# GPS_radiologger_v14.net
KiCad netlist of a schematic drawn in EAGLE
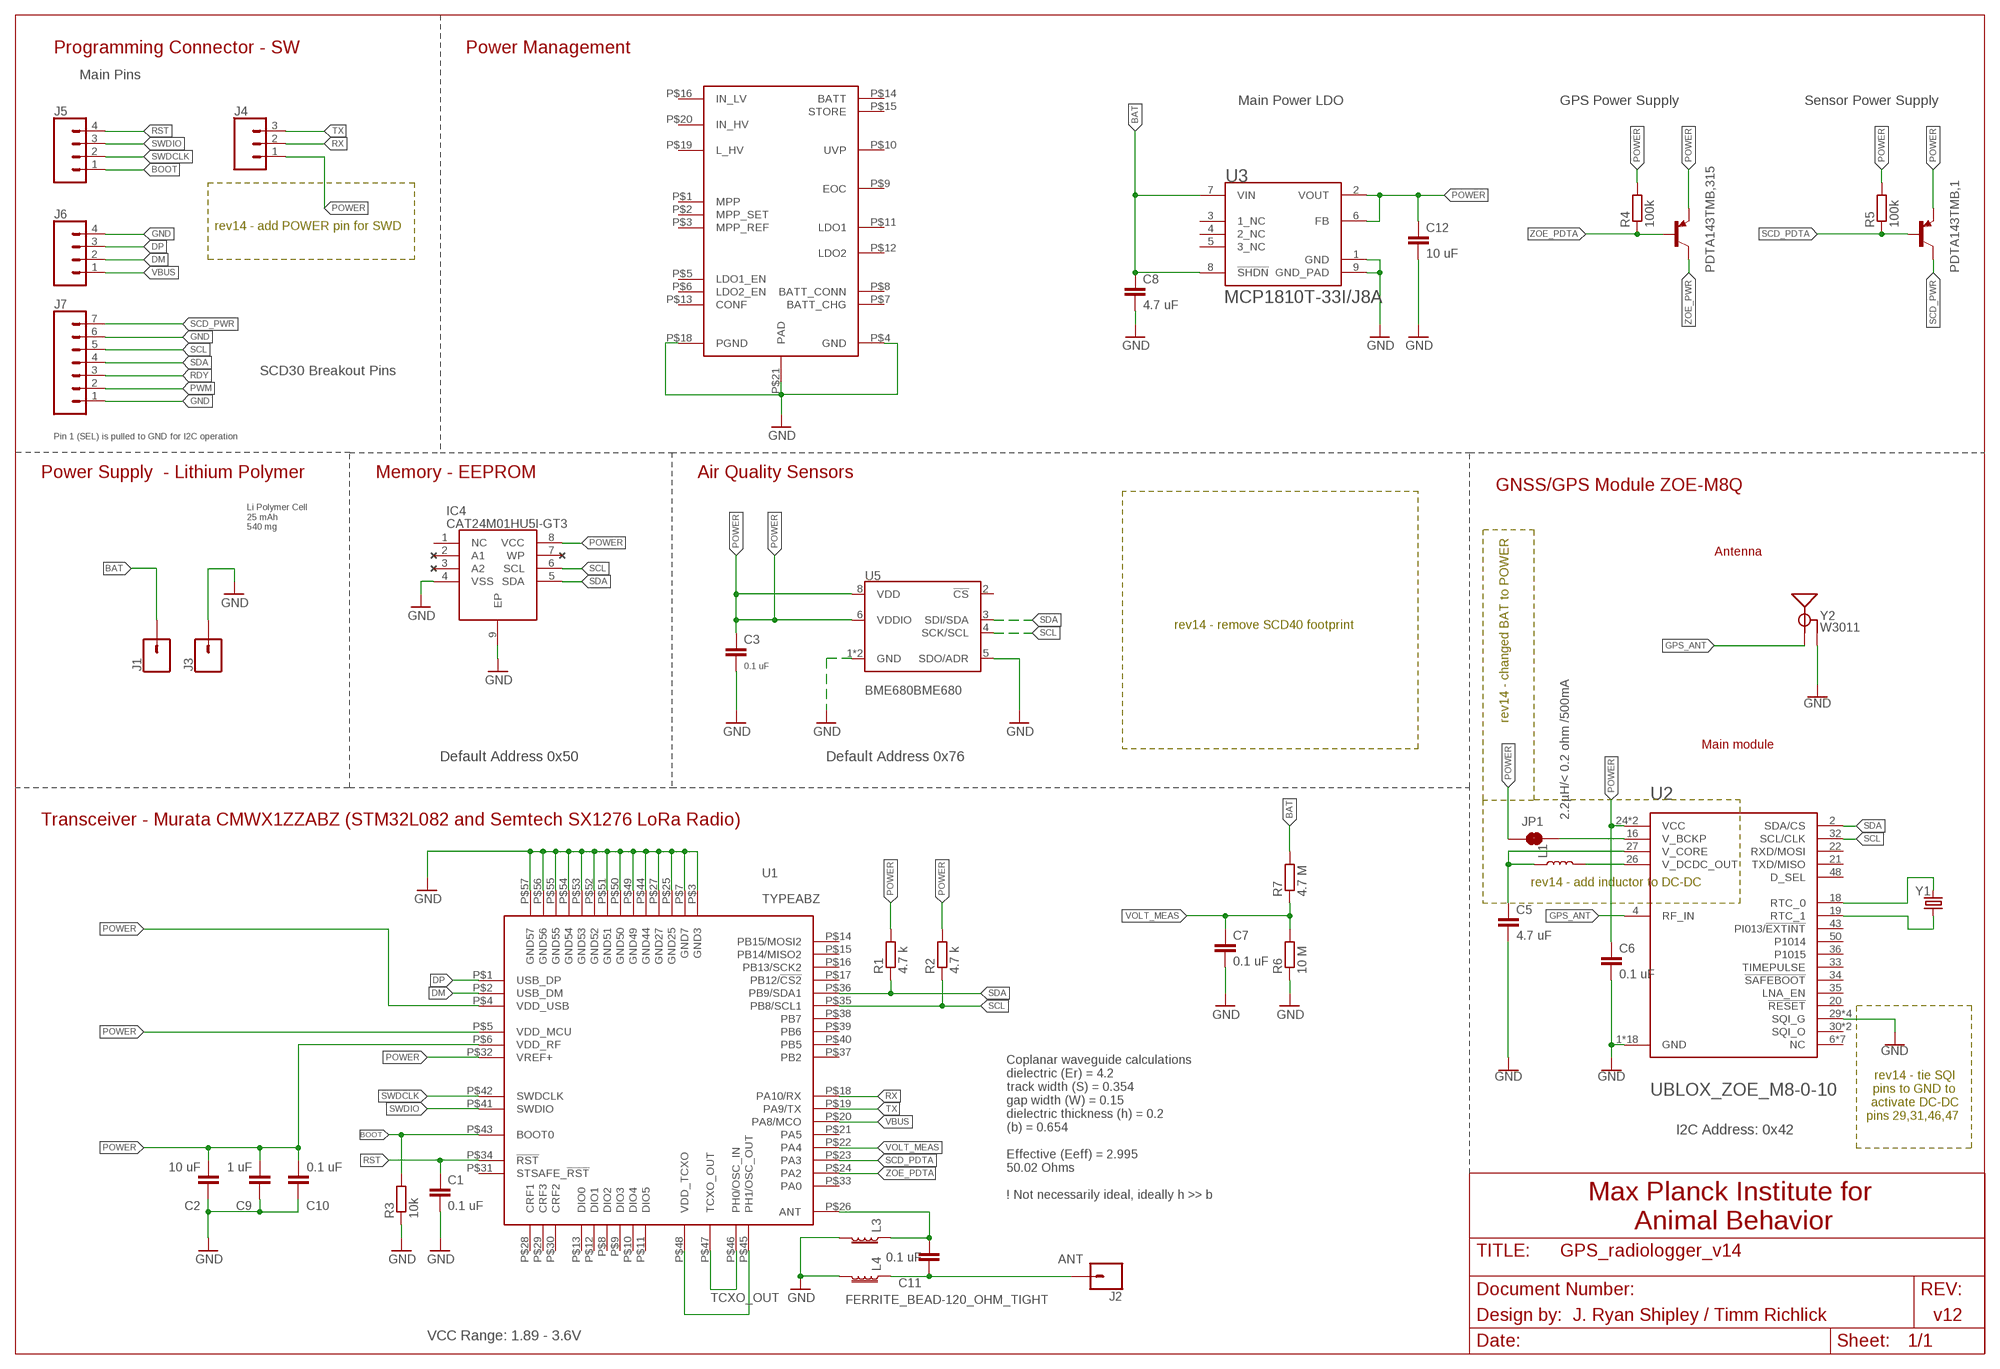
[diagram p0: schematic, sheet 1]

(export (version "E")
  (design (tool "Eeschema 10.0.6"))
  (components
    (comp (ref "C1")
      (value "0.1 uF")
      (footprint "eagle-import:C0201")
      (libsource (lib "eagle-import") (part "C-EUC0201"))
    )
    (comp (ref "C2")
      (value "10 uF")
      (footprint "eagle-import:C0201")
      (libsource (lib "eagle-import") (part "C-EUC0201"))
    )
    (comp (ref "C3")
      (value "0.1 uF")
      (footprint "eagle-import:C0201")
      (libsource (lib "eagle-import") (part "C-EUC0201"))
    )
    (comp (ref "C5")
      (value "4.7 uF")
      (footprint "eagle-import:C0201")
      (libsource (lib "eagle-import") (part "C-EUC0201"))
    )
    (comp (ref "C6")
      (value "0.1 uF")
      (footprint "eagle-import:C0201")
      (libsource (lib "eagle-import") (part "C-EUC0201"))
    )
    (comp (ref "C7")
      (value "0.1 uF")
      (footprint "eagle-import:C0201")
      (libsource (lib "eagle-import") (part "C-EUC0201"))
    )
    (comp (ref "C8")
      (value "4.7 uF")
      (footprint "eagle-import:C0201")
      (libsource (lib "eagle-import") (part "C-EUC0201"))
    )
    (comp (ref "C9")
      (value "1 uF")
      (footprint "eagle-import:C0201")
      (libsource (lib "eagle-import") (part "C-EUC0201"))
    )
    (comp (ref "C10")
      (value "0.1 uF")
      (footprint "eagle-import:C0201")
      (libsource (lib "eagle-import") (part "C-EUC0201"))
    )
    (comp (ref "C11")
      (value "0.1 uF")
      (footprint "eagle-import:C0201")
      (libsource (lib "eagle-import") (part "C-EUC0201"))
    )
    (comp (ref "C12")
      (value "10 uF")
      (footprint "eagle-import:C0201")
      (libsource (lib "eagle-import") (part "C-EUC0201"))
    )
    (comp (ref "IC4")
      (value "CAT24M01HU5I-GT3")
      (footprint "eagle-import:SON50P300X200X55-9N")
      (fields
        (field (name "MOUSER_PART_NUMBER") "863-CAT24M01HU5I-GT3")
        (field (name "RS_PART_NUMBER") "7814831P")
      )
      (libsource (lib "eagle-import") (part "CAT24M01HU5I-GT3"))
    )
    (comp (ref "J1")
      (value "CONN_01PTH_NO_SILK_YES_STOP")
      (footprint "eagle-import:1X01_NO_SILK")
      (libsource (lib "eagle-import") (part "CONN_01PTH_NO_SILK_YES_STOP"))
    )
    (comp (ref "J2")
      (value "CONN_01PTH_NO_SILK_SMALL")
      (footprint "eagle-import:1X01_SMALL")
      (libsource (lib "eagle-import") (part "CONN_01PTH_NO_SILK_SMALL"))
    )
    (comp (ref "J3")
      (value "CONN_01PTH_NO_SILK_YES_STOP")
      (footprint "eagle-import:1X01_NO_SILK")
      (libsource (lib "eagle-import") (part "CONN_01PTH_NO_SILK_YES_STOP"))
    )
    (comp (ref "J4")
      (value "CONN_031X03_1.27_NO_SILK")
      (footprint "eagle-import:1X03_1.27MM_NO_SILK")
      (libsource (lib "eagle-import") (part "CONN_031X03_1.27_NO_SILK"))
    )
    (comp (ref "J5")
      (value "CONN_041.27MM_NO_SILK")
      (footprint "eagle-import:1X04_1.27MM_NO_SILK")
      (libsource (lib "eagle-import") (part "CONN_041.27MM_NO_SILK"))
    )
    (comp (ref "J6")
      (value "CONN_041.27MM_NO_SILK")
      (footprint "eagle-import:1X04_1.27MM_NO_SILK")
      (libsource (lib "eagle-import") (part "CONN_041.27MM_NO_SILK"))
    )
    (comp (ref "J7")
      (value "CONN_07NO_SILK")
      (footprint "eagle-import:1X07_NO_SILK")
      (libsource (lib "eagle-import") (part "CONN_07NO_SILK"))
    )
    (comp (ref "JP1")
      (value "JUMPER-SMT_2_NC_TRACE_NO-SILK")
      (footprint "eagle-import:SMT-JUMPER_2_NC_TRACE_NO-SILK")
      (libsource (lib "eagle-import") (part "JUMPER-SMT_2_NC_TRACE_NO-SILK"))
    )
    (comp (ref "L1")
      (value "2.2µH/< 0.2 ohm /500mA")
      (footprint "eagle-import:0805")
      (libsource (lib "eagle-import") (part "INDUCTOR-0805-3.3UH"))
    )
    (comp (ref "L3")
      (value "FERRITE_BEAD-120_OHM_TIGHT")
      (footprint "eagle-import:0402-TIGHT")
      (libsource (lib "eagle-import") (part "FERRITE_BEAD-120_OHM_TIGHT"))
    )
    (comp (ref "L4")
      (value "FERRITE_BEAD-120_OHM_TIGHT")
      (footprint "eagle-import:0402-TIGHT")
      (libsource (lib "eagle-import") (part "FERRITE_BEAD-120_OHM_TIGHT"))
    )
    (comp (ref "PDTA143TMB,1")
      (value "TINYPICO-PNPAMB")
      (footprint "eagle-import:SOT883(B)")
      (libsource (lib "eagle-import") (part "TINYPICO-PNPMBA"))
    )
    (comp (ref "PDTA143TMB,315")
      (value "TINYPICO-PNPAMB")
      (footprint "eagle-import:SOT883(B)")
      (libsource (lib "eagle-import") (part "TINYPICO-PNPMBA"))
    )
    (comp (ref "R1")
      (value "4.7 k")
      (footprint "eagle-import:R0201")
      (libsource (lib "eagle-import") (part "R-EU_R0201"))
    )
    (comp (ref "R2")
      (value "4.7 k")
      (footprint "eagle-import:R0201")
      (libsource (lib "eagle-import") (part "R-EU_R0201"))
    )
    (comp (ref "R3")
      (value "10k")
      (footprint "eagle-import:R0201")
      (libsource (lib "eagle-import") (part "R-EU_R0201"))
    )
    (comp (ref "R4")
      (value "100k")
      (footprint "eagle-import:R0201")
      (libsource (lib "eagle-import") (part "R-EU_R0201"))
    )
    (comp (ref "R5")
      (value "100k")
      (footprint "eagle-import:R0201")
      (libsource (lib "eagle-import") (part "R-EU_R0201"))
    )
    (comp (ref "R6")
      (value "10 M")
      (footprint "eagle-import:R0201")
      (libsource (lib "eagle-import") (part "R-EU_R0201"))
    )
    (comp (ref "R7")
      (value "4.7 M")
      (footprint "eagle-import:R0201")
      (libsource (lib "eagle-import") (part "R-EU_R0201"))
    )
    (comp (ref "U1")
      (value "TYPEABZ")
      (footprint "eagle-import:TYPEABZ")
      (libsource (lib "eagle-import") (part "TYPEABZ"))
    )
    (comp (ref "U2")
      (value "UBLOX_ZOE_M8-0-10")
      (footprint "eagle-import:UBLOX_ZOE_M8-0-10")
      (libsource (lib "eagle-import") (part "UBLOX_ZOE_M8-0-10"))
    )
    (comp (ref "U3")
      (value "MICROCHIP_MCP1810T-33I-J8AMICROCHIP_MCP1810T-33I-J8A_0_0")
      (footprint "eagle-import:MICROCHIP_MCP1810T-33I-J8A_0")
      (fields
        (field (name "DIGIKEY_PART_NUMBER") "MCP1810T-33I/J8ACT-ND")
        (field (name "MF") "Microchip")
        (field (name "MOUSER_PART_NUMBER") "579-MCP1810T-33I/J8A")
      )
      (libsource (lib "eagle-import") (part "MICROCHIP_MCP1810T-33I-J8AMICROCHIP_MCP1810T-33I-J8A_0_0"))
    )
    (comp (ref "U4")
      (value "SPV1050")
      (footprint "eagle-import:SPV1050")
      (libsource (lib "eagle-import") (part "SPV1050"))
    )
    (comp (ref "U5")
      (value "BME680BME680")
      (footprint "eagle-import:LGA3.0X3.0")
      (libsource (lib "eagle-import") (part "BME680BME680"))
    )
    (comp (ref "Y1")
      (value "32.768kHz")
      (footprint "eagle-import:CRYSTAL-SMD-1.0X1.2MM")
      (libsource (lib "eagle-import") (part "CRYSTAL-32.768KHZ"))
    )
    (comp (ref "Y2")
      (value "W3011")
      (footprint "eagle-import:W3011")
      (libsource (lib "eagle-import") (part "GPS_CHIP_ANTENNAW3011"))
    )
  )
  (nets
    (net (code "1") (name "/ANT") (class "Default")
      (node (ref "C11") (pin "1") (pinfunction "1_1") (pintype "passive"))
      (node (ref "J2") (pin "P$1") (pinfunction "1_P$1") (pintype "passive"))
      (node (ref "L4") (pin "1") (pinfunction "1_1") (pintype "passive"))
    )
    (net (code "2") (name "/IN_HV") (class "Default")
      (node (ref "U4") (pin "P$20") (pinfunction "IN_HV_P$20") (pintype "power_in"))
    )
    (net (code "3") (name "/IN_LV") (class "Default")
      (node (ref "U4") (pin "P$16") (pinfunction "IN_LV_P$16") (pintype "power_in"))
    )
    (net (code "4") (name "/L_HV") (class "Default")
      (node (ref "U4") (pin "P$19") (pinfunction "L_HV_P$19") (pintype "power_in"))
    )
    (net (code "5") (name "/TCXO_OUT") (class "Default")
      (node (ref "U1") (pin "P$46") (pinfunction "PH0/OSC_IN_P$46") (pintype "bidirectional"))
      (node (ref "U1") (pin "P$47") (pinfunction "TCXO_OUT_P$47") (pintype "bidirectional"))
    )
    (net (code "6") (name "BAT") (class "Default")
      (node (ref "C8") (pin "1") (pinfunction "1_1") (pintype "passive"))
      (node (ref "J1") (pin "1") (pinfunction "1_1") (pintype "passive"))
      (node (ref "R7") (pin "2") (pinfunction "2_2") (pintype "passive"))
      (node (ref "U3") (pin "7") (pinfunction "VIN_7") (pintype "bidirectional"))
      (node (ref "U3") (pin "8") (pinfunction "~{SHDN}_8") (pintype "bidirectional"))
    )
    (net (code "7") (name "BOOT") (class "Default")
      (node (ref "J5") (pin "1") (pinfunction "1_1") (pintype "passive"))
      (node (ref "R3") (pin "2") (pinfunction "2_2") (pintype "passive"))
      (node (ref "U1") (pin "P$43") (pinfunction "BOOT0_P$43") (pintype "bidirectional"))
    )
    (net (code "8") (name "DM") (class "Default")
      (node (ref "J6") (pin "2") (pinfunction "2_2") (pintype "passive"))
      (node (ref "U1") (pin "P$2") (pinfunction "USB_DM_P$2") (pintype "bidirectional"))
    )
    (net (code "9") (name "DP") (class "Default")
      (node (ref "J6") (pin "3") (pinfunction "3_3") (pintype "passive"))
      (node (ref "U1") (pin "P$1") (pinfunction "USB_DP_P$1") (pintype "bidirectional"))
    )
    (net (code "10") (name "GND") (class "Default")
      (node (ref "C1") (pin "2") (pinfunction "2_2") (pintype "passive"))
      (node (ref "C10") (pin "1") (pinfunction "1_1") (pintype "passive"))
      (node (ref "C12") (pin "2") (pinfunction "2_2") (pintype "passive"))
      (node (ref "C2") (pin "1") (pinfunction "1_1") (pintype "passive"))
      (node (ref "C3") (pin "2") (pinfunction "2_2") (pintype "passive"))
      (node (ref "C5") (pin "2") (pinfunction "2_2") (pintype "passive"))
      (node (ref "C6") (pin "2") (pinfunction "2_2") (pintype "passive"))
      (node (ref "C7") (pin "2") (pinfunction "2_2") (pintype "passive"))
      (node (ref "C8") (pin "2") (pinfunction "2_2") (pintype "passive"))
      (node (ref "C9") (pin "1") (pinfunction "1_1") (pintype "passive"))
      (node (ref "IC4") (pin "4") (pinfunction "VSS_4") (pintype "power_in"))
      (node (ref "IC4") (pin "9") (pinfunction "EP_9") (pintype "bidirectional"))
      (node (ref "J3") (pin "1") (pinfunction "1_1") (pintype "passive"))
      (node (ref "J6") (pin "4") (pinfunction "4_4") (pintype "passive"))
      (node (ref "J7") (pin "1") (pinfunction "1_1") (pintype "passive"))
      (node (ref "J7") (pin "6") (pinfunction "6_6") (pintype "passive"))
      (node (ref "L3") (pin "2") (pinfunction "2_2") (pintype "passive"))
      (node (ref "L4") (pin "2") (pinfunction "2_2") (pintype "passive"))
      (node (ref "R3") (pin "1") (pinfunction "1_1") (pintype "passive"))
      (node (ref "R6") (pin "1") (pinfunction "1_1") (pintype "passive"))
      (node (ref "U1") (pin "P$25") (pinfunction "GND25_P$25") (pintype "power_in"))
      (node (ref "U1") (pin "P$27") (pinfunction "GND27_P$27") (pintype "power_in"))
      (node (ref "U1") (pin "P$3") (pinfunction "GND3_P$3") (pintype "power_in"))
      (node (ref "U1") (pin "P$44") (pinfunction "GND44_P$44") (pintype "power_in"))
      (node (ref "U1") (pin "P$49") (pinfunction "GND49_P$49") (pintype "power_in"))
      (node (ref "U1") (pin "P$50") (pinfunction "GND50_P$50") (pintype "power_in"))
      (node (ref "U1") (pin "P$51") (pinfunction "GND51_P$51") (pintype "power_in"))
      (node (ref "U1") (pin "P$52") (pinfunction "GND52_P$52") (pintype "power_in"))
      (node (ref "U1") (pin "P$53") (pinfunction "GND53_P$53") (pintype "power_in"))
      (node (ref "U1") (pin "P$54") (pinfunction "GND54_P$54") (pintype "power_in"))
      (node (ref "U1") (pin "P$55") (pinfunction "GND55_P$55") (pintype "power_in"))
      (node (ref "U1") (pin "P$56") (pinfunction "GND56_P$56") (pintype "power_in"))
      (node (ref "U1") (pin "P$57") (pinfunction "GND57_P$57") (pintype "power_in"))
      (node (ref "U1") (pin "P$7") (pinfunction "GND7_P$7") (pintype "power_in"))
      (node (ref "U2") (pin "1") (pinfunction "GND_1") (pintype "power_in"))
      (node (ref "U2") (pin "10") (pinfunction "GND_10") (pintype "power_in"))
      (node (ref "U2") (pin "11") (pinfunction "GND_11") (pintype "power_in"))
      (node (ref "U2") (pin "12") (pinfunction "GND_12") (pintype "power_in"))
      (node (ref "U2") (pin "17") (pinfunction "GND_17") (pintype "power_in"))
      (node (ref "U2") (pin "23") (pinfunction "GND_23") (pintype "power_in"))
      (node (ref "U2") (pin "29") (pinfunction "SQI_G_29") (pintype "bidirectional"))
      (node (ref "U2") (pin "3") (pinfunction "GND_3") (pintype "power_in"))
      (node (ref "U2") (pin "31") (pinfunction "SQI_G_31") (pintype "bidirectional"))
      (node (ref "U2") (pin "37") (pinfunction "GND_37") (pintype "power_in"))
      (node (ref "U2") (pin "38") (pinfunction "GND_38") (pintype "power_in"))
      (node (ref "U2") (pin "39") (pinfunction "GND_39") (pintype "power_in"))
      (node (ref "U2") (pin "40") (pinfunction "GND_40") (pintype "power_in"))
      (node (ref "U2") (pin "41") (pinfunction "GND_41") (pintype "power_in"))
      (node (ref "U2") (pin "44") (pinfunction "GND_44") (pintype "power_in"))
      (node (ref "U2") (pin "46") (pinfunction "SQI_G_46") (pintype "bidirectional"))
      (node (ref "U2") (pin "47") (pinfunction "SQI_G_47") (pintype "bidirectional"))
      (node (ref "U2") (pin "49") (pinfunction "GND_49") (pintype "power_in"))
      (node (ref "U2") (pin "5") (pinfunction "GND_5") (pintype "power_in"))
      (node (ref "U2") (pin "7") (pinfunction "GND_7") (pintype "power_in"))
      (node (ref "U2") (pin "8") (pinfunction "GND_8") (pintype "power_in"))
      (node (ref "U2") (pin "9") (pinfunction "GND_9") (pintype "power_in"))
      (node (ref "U3") (pin "1") (pinfunction "GND_1") (pintype "bidirectional"))
      (node (ref "U3") (pin "9") (pinfunction "GND_PAD_9") (pintype "bidirectional"))
      (node (ref "U4") (pin "P$18") (pinfunction "PGND_P$18") (pintype "power_in"))
      (node (ref "U4") (pin "P$21") (pinfunction "PAD_P$21") (pintype "power_in"))
      (node (ref "U4") (pin "P$4") (pinfunction "GND_P$4") (pintype "power_in"))
      (node (ref "U5") (pin "1") (pinfunction "GND_1") (pintype "bidirectional"))
      (node (ref "U5") (pin "5") (pinfunction "SDO/ADR_5") (pintype "bidirectional"))
      (node (ref "U5") (pin "7") (pinfunction "GND_7") (pintype "bidirectional"))
      (node (ref "Y2") (pin "2") (pinfunction "GND_2") (pintype "bidirectional"))
      (node (ref "Y2") (pin "3") (pinfunction "GND_3") (pintype "bidirectional"))
    )
    (net (code "11") (name "GPS_ANT") (class "Default")
      (node (ref "U2") (pin "4") (pinfunction "RF_IN_4") (pintype "bidirectional"))
      (node (ref "Y2") (pin "1") (pinfunction "SIGNAL_1") (pintype "bidirectional"))
    )
    (net (code "12") (name "Net-(U1-ANT)") (class "Default")
      (node (ref "C11") (pin "2") (pinfunction "2_2") (pintype "passive"))
      (node (ref "L3") (pin "1") (pinfunction "1_1") (pintype "passive"))
      (node (ref "U1") (pin "P$26") (pinfunction "ANT_P$26") (pintype "bidirectional"))
    )
    (net (code "13") (name "Net-(U1-PH1{slash}OSC_OUT)") (class "Default")
      (node (ref "U1") (pin "P$45") (pinfunction "PH1/OSC_OUT_P$45") (pintype "bidirectional"))
      (node (ref "U1") (pin "P$48") (pinfunction "VDD_TCXO_P$48") (pintype "power_in"))
    )
    (net (code "14") (name "Net-(U2-RTC_0)") (class "Default")
      (node (ref "U2") (pin "18") (pinfunction "RTC_0_18") (pintype "bidirectional"))
      (node (ref "Y1") (pin "P$2") (pinfunction "2_P$2") (pintype "passive"))
    )
    (net (code "15") (name "Net-(U2-RTC_1)") (class "Default")
      (node (ref "U2") (pin "19") (pinfunction "RTC_1_19") (pintype "bidirectional"))
      (node (ref "Y1") (pin "P$1") (pinfunction "1_P$1") (pintype "passive"))
    )
    (net (code "16") (name "Net-(U2-V_BCKP)") (class "Default")
      (node (ref "JP1") (pin "2") (pinfunction "2_2") (pintype "passive"))
      (node (ref "U2") (pin "16") (pinfunction "V_BCKP_16") (pintype "power_in"))
    )
    (net (code "17") (name "Net-(U2-V_CORE)") (class "Default")
      (node (ref "C5") (pin "1") (pinfunction "1_1") (pintype "passive"))
      (node (ref "L1") (pin "1") (pinfunction "1_1") (pintype "passive"))
      (node (ref "U2") (pin "27") (pinfunction "V_CORE_27") (pintype "power_in"))
    )
    (net (code "18") (name "Net-(U2-V_DCDC_OUT)") (class "Default")
      (node (ref "L1") (pin "2") (pinfunction "2_2") (pintype "passive"))
      (node (ref "U2") (pin "26") (pinfunction "V_DCDC_OUT_26") (pintype "power_in"))
    )
    (net (code "19") (name "POWER") (class "Default")
      (node (ref "C10") (pin "2") (pinfunction "2_2") (pintype "passive"))
      (node (ref "C12") (pin "1") (pinfunction "1_1") (pintype "passive"))
      (node (ref "C2") (pin "2") (pinfunction "2_2") (pintype "passive"))
      (node (ref "C3") (pin "1") (pinfunction "1_1") (pintype "passive"))
      (node (ref "C6") (pin "1") (pinfunction "1_1") (pintype "passive"))
      (node (ref "C9") (pin "2") (pinfunction "2_2") (pintype "passive"))
      (node (ref "IC4") (pin "8") (pinfunction "VCC_8") (pintype "power_in"))
      (node (ref "J4") (pin "1") (pinfunction "1_1") (pintype "passive"))
      (node (ref "JP1") (pin "1") (pinfunction "1_1") (pintype "passive"))
      (node (ref "PDTA143TMB,1") (pin "2") (pinfunction "E_2") (pintype "passive"))
      (node (ref "PDTA143TMB,315") (pin "2") (pinfunction "E_2") (pintype "passive"))
      (node (ref "R1") (pin "2") (pinfunction "2_2") (pintype "passive"))
      (node (ref "R2") (pin "2") (pinfunction "2_2") (pintype "passive"))
      (node (ref "R4") (pin "2") (pinfunction "2_2") (pintype "passive"))
      (node (ref "R5") (pin "2") (pinfunction "2_2") (pintype "passive"))
      (node (ref "U1") (pin "P$32") (pinfunction "VREF+_P$32") (pintype "power_in"))
      (node (ref "U1") (pin "P$4") (pinfunction "VDD_USB_P$4") (pintype "power_in"))
      (node (ref "U1") (pin "P$5") (pinfunction "VDD_MCU_P$5") (pintype "power_in"))
      (node (ref "U1") (pin "P$6") (pinfunction "VDD_RF_P$6") (pintype "power_in"))
      (node (ref "U2") (pin "24") (pinfunction "VCC_24") (pintype "power_in"))
      (node (ref "U2") (pin "25") (pinfunction "VCC_25") (pintype "power_in"))
      (node (ref "U3") (pin "2") (pinfunction "VOUT_2") (pintype "bidirectional"))
      (node (ref "U3") (pin "6") (pinfunction "FB_6") (pintype "bidirectional"))
      (node (ref "U5") (pin "6") (pinfunction "VDDIO_6") (pintype "bidirectional"))
      (node (ref "U5") (pin "8") (pinfunction "VDD_8") (pintype "bidirectional"))
    )
    (net (code "20") (name "PWM") (class "Default")
      (node (ref "J7") (pin "2") (pinfunction "2_2") (pintype "passive"))
    )
    (net (code "21") (name "RDY") (class "Default")
      (node (ref "J7") (pin "3") (pinfunction "3_3") (pintype "passive"))
    )
    (net (code "22") (name "RST") (class "Default")
      (node (ref "C1") (pin "1") (pinfunction "1_1") (pintype "passive"))
      (node (ref "J5") (pin "4") (pinfunction "4_4") (pintype "passive"))
      (node (ref "U1") (pin "P$34") (pinfunction "~{RST}_P$34") (pintype "bidirectional"))
    )
    (net (code "23") (name "RX") (class "Default")
      (node (ref "J4") (pin "2") (pinfunction "2_2") (pintype "passive"))
      (node (ref "U1") (pin "P$18") (pinfunction "PA10/RX_P$18") (pintype "bidirectional"))
    )
    (net (code "24") (name "SCD_PDTA") (class "Default")
      (node (ref "PDTA143TMB,1") (pin "1") (pinfunction "B_1") (pintype "passive"))
      (node (ref "R5") (pin "1") (pinfunction "1_1") (pintype "passive"))
      (node (ref "U1") (pin "P$23") (pinfunction "PA3_P$23") (pintype "bidirectional"))
    )
    (net (code "25") (name "SCD_PWR") (class "Default")
      (node (ref "J7") (pin "7") (pinfunction "7_7") (pintype "passive"))
      (node (ref "PDTA143TMB,1") (pin "3") (pinfunction "C_3") (pintype "passive"))
    )
    (net (code "26") (name "SCL") (class "Default")
      (node (ref "IC4") (pin "6") (pinfunction "SCL_6") (pintype "bidirectional"))
      (node (ref "J7") (pin "5") (pinfunction "5_5") (pintype "passive"))
      (node (ref "R2") (pin "1") (pinfunction "1_1") (pintype "passive"))
      (node (ref "U1") (pin "P$35") (pinfunction "PB8/SCL1_P$35") (pintype "bidirectional"))
      (node (ref "U2") (pin "32") (pinfunction "SCL/CLK_32") (pintype "bidirectional"))
      (node (ref "U5") (pin "4") (pinfunction "SCK/SCL_4") (pintype "bidirectional"))
    )
    (net (code "27") (name "SDA") (class "Default")
      (node (ref "IC4") (pin "5") (pinfunction "SDA_5") (pintype "bidirectional"))
      (node (ref "J7") (pin "4") (pinfunction "4_4") (pintype "passive"))
      (node (ref "R1") (pin "1") (pinfunction "1_1") (pintype "passive"))
      (node (ref "U1") (pin "P$36") (pinfunction "PB9/SDA1_P$36") (pintype "bidirectional"))
      (node (ref "U2") (pin "2") (pinfunction "SDA/CS_2") (pintype "bidirectional"))
      (node (ref "U5") (pin "3") (pinfunction "SDI/SDA_3") (pintype "bidirectional"))
    )
    (net (code "28") (name "SWDCLK") (class "Default")
      (node (ref "J5") (pin "2") (pinfunction "2_2") (pintype "passive"))
      (node (ref "U1") (pin "P$42") (pinfunction "SWDCLK_P$42") (pintype "bidirectional"))
    )
    (net (code "29") (name "SWDIO") (class "Default")
      (node (ref "J5") (pin "3") (pinfunction "3_3") (pintype "passive"))
      (node (ref "U1") (pin "P$41") (pinfunction "SWDIO_P$41") (pintype "bidirectional"))
    )
    (net (code "30") (name "TX") (class "Default")
      (node (ref "J4") (pin "3") (pinfunction "3_3") (pintype "passive"))
      (node (ref "U1") (pin "P$19") (pinfunction "PA9/TX_P$19") (pintype "bidirectional"))
    )
    (net (code "31") (name "VBUS") (class "Default")
      (node (ref "J6") (pin "1") (pinfunction "1_1") (pintype "passive"))
      (node (ref "U1") (pin "P$20") (pinfunction "PA8/MCO_P$20") (pintype "bidirectional"))
    )
    (net (code "32") (name "VOLT_MEAS") (class "Default")
      (node (ref "C7") (pin "1") (pinfunction "1_1") (pintype "passive"))
      (node (ref "R6") (pin "2") (pinfunction "2_2") (pintype "passive"))
      (node (ref "R7") (pin "1") (pinfunction "1_1") (pintype "passive"))
      (node (ref "U1") (pin "P$22") (pinfunction "PA4_P$22") (pintype "bidirectional"))
    )
    (net (code "33") (name "ZOE_PDTA") (class "Default")
      (node (ref "PDTA143TMB,315") (pin "1") (pinfunction "B_1") (pintype "passive"))
      (node (ref "R4") (pin "1") (pinfunction "1_1") (pintype "passive"))
      (node (ref "U1") (pin "P$24") (pinfunction "PA2_P$24") (pintype "bidirectional"))
    )
    (net (code "34") (name "ZOE_PWR") (class "Default")
      (node (ref "PDTA143TMB,315") (pin "3") (pinfunction "C_3") (pintype "passive"))
    )
    (net (code "35") (name "unconnected-(IC4-A1-Pad2)") (class "Default")
      (node (ref "IC4") (pin "2") (pinfunction "A1_2") (pintype "bidirectional"))
    )
    (net (code "36") (name "unconnected-(IC4-A2-Pad3)") (class "Default")
      (node (ref "IC4") (pin "3") (pinfunction "A2_3") (pintype "bidirectional"))
    )
    (net (code "37") (name "unconnected-(IC4-NC-Pad1)") (class "Default")
      (node (ref "IC4") (pin "1") (pinfunction "NC_1") (pintype "no_connect"))
    )
    (net (code "38") (name "unconnected-(IC4-WP-Pad7)") (class "Default")
      (node (ref "IC4") (pin "7") (pinfunction "WP_7") (pintype "bidirectional"))
    )
    (net (code "39") (name "unconnected-(U1-CRF1-PadP$28)") (class "Default")
      (node (ref "U1") (pin "P$28") (pinfunction "CRF1_P$28") (pintype "no_connect"))
    )
    (net (code "40") (name "unconnected-(U1-CRF2-PadP$30)") (class "Default")
      (node (ref "U1") (pin "P$30") (pinfunction "CRF2_P$30") (pintype "no_connect"))
    )
    (net (code "41") (name "unconnected-(U1-CRF3-PadP$29)") (class "Default")
      (node (ref "U1") (pin "P$29") (pinfunction "CRF3_P$29") (pintype "no_connect"))
    )
    (net (code "42") (name "unconnected-(U1-DIO0-PadP$13)") (class "Default")
      (node (ref "U1") (pin "P$13") (pinfunction "DIO0_P$13") (pintype "no_connect"))
    )
    (net (code "43") (name "unconnected-(U1-DIO1-PadP$12)") (class "Default")
      (node (ref "U1") (pin "P$12") (pinfunction "DIO1_P$12") (pintype "no_connect"))
    )
    (net (code "44") (name "unconnected-(U1-DIO2-PadP$8)") (class "Default")
      (node (ref "U1") (pin "P$8") (pinfunction "DIO2_P$8") (pintype "no_connect"))
    )
    (net (code "45") (name "unconnected-(U1-DIO3-PadP$9)") (class "Default")
      (node (ref "U1") (pin "P$9") (pinfunction "DIO3_P$9") (pintype "no_connect"))
    )
    (net (code "46") (name "unconnected-(U1-DIO4-PadP$10)") (class "Default")
      (node (ref "U1") (pin "P$10") (pinfunction "DIO4_P$10") (pintype "bidirectional"))
    )
    (net (code "47") (name "unconnected-(U1-DIO5-PadP$11)") (class "Default")
      (node (ref "U1") (pin "P$11") (pinfunction "DIO5_P$11") (pintype "bidirectional"))
    )
    (net (code "48") (name "unconnected-(U1-PA0-PadP$33)") (class "Default")
      (node (ref "U1") (pin "P$33") (pinfunction "PA0_P$33") (pintype "bidirectional"))
    )
    (net (code "49") (name "unconnected-(U1-PA5-PadP$21)") (class "Default")
      (node (ref "U1") (pin "P$21") (pinfunction "PA5_P$21") (pintype "bidirectional"))
    )
    (net (code "50") (name "unconnected-(U1-PB2-PadP$37)") (class "Default")
      (node (ref "U1") (pin "P$37") (pinfunction "PB2_P$37") (pintype "bidirectional"))
    )
    (net (code "51") (name "unconnected-(U1-PB5-PadP$40)") (class "Default")
      (node (ref "U1") (pin "P$40") (pinfunction "PB5_P$40") (pintype "bidirectional"))
    )
    (net (code "52") (name "unconnected-(U1-PB6-PadP$39)") (class "Default")
      (node (ref "U1") (pin "P$39") (pinfunction "PB6_P$39") (pintype "bidirectional"))
    )
    (net (code "53") (name "unconnected-(U1-PB7-PadP$38)") (class "Default")
      (node (ref "U1") (pin "P$38") (pinfunction "PB7_P$38") (pintype "bidirectional"))
    )
    (net (code "54") (name "unconnected-(U1-PB12{slash}~{CS2}-PadP$17)") (class "Default")
      (node (ref "U1") (pin "P$17") (pinfunction "PB12/~{CS2}_P$17") (pintype "bidirectional"))
    )
    (net (code "55") (name "unconnected-(U1-PB13{slash}SCK2-PadP$16)") (class "Default")
      (node (ref "U1") (pin "P$16") (pinfunction "PB13/SCK2_P$16") (pintype "bidirectional"))
    )
    (net (code "56") (name "unconnected-(U1-PB14{slash}MISO2-PadP$15)") (class "Default")
      (node (ref "U1") (pin "P$15") (pinfunction "PB14/MISO2_P$15") (pintype "bidirectional"))
    )
    (net (code "57") (name "unconnected-(U1-PB15{slash}MOSI2-PadP$14)") (class "Default")
      (node (ref "U1") (pin "P$14") (pinfunction "PB15/MOSI2_P$14") (pintype "bidirectional"))
    )
    (net (code "58") (name "unconnected-(U1-STSAFE_~{RST}-PadP$31)") (class "Default")
      (node (ref "U1") (pin "P$31") (pinfunction "STSAFE_~{RST}_P$31") (pintype "bidirectional"))
    )
    (net (code "59") (name "unconnected-(U2-D_SEL-Pad48)") (class "Default")
      (node (ref "U2") (pin "48") (pinfunction "D_SEL_48") (pintype "bidirectional"))
    )
    (net (code "60") (name "unconnected-(U2-LNA_EN-Pad35)") (class "Default")
      (node (ref "U2") (pin "35") (pinfunction "LNA_EN_35") (pintype "bidirectional"))
    )
    (net (code "61") (name "unconnected-(U2-NC-Pad6)") (class "Default")
      (node (ref "U2") (pin "6") (pinfunction "NC_6") (pintype "no_connect"))
    )
    (net (code "62") (name "unconnected-(U2-NC-Pad13)") (class "Default")
      (node (ref "U2") (pin "13") (pinfunction "NC_13") (pintype "no_connect"))
    )
    (net (code "63") (name "unconnected-(U2-NC-Pad14)") (class "Default")
      (node (ref "U2") (pin "14") (pinfunction "NC_14") (pintype "no_connect"))
    )
    (net (code "64") (name "unconnected-(U2-NC-Pad15)") (class "Default")
      (node (ref "U2") (pin "15") (pinfunction "NC_15") (pintype "no_connect"))
    )
    (net (code "65") (name "unconnected-(U2-NC-Pad28)") (class "Default")
      (node (ref "U2") (pin "28") (pinfunction "NC_28") (pintype "no_connect"))
    )
    (net (code "66") (name "unconnected-(U2-NC-Pad42)") (class "Default")
      (node (ref "U2") (pin "42") (pinfunction "NC_42") (pintype "no_connect"))
    )
    (net (code "67") (name "unconnected-(U2-NC-Pad51)") (class "Default")
      (node (ref "U2") (pin "51") (pinfunction "NC_51") (pintype "no_connect"))
    )
    (net (code "68") (name "unconnected-(U2-P1014-Pad50)") (class "Default")
      (node (ref "U2") (pin "50") (pinfunction "P1014_50") (pintype "bidirectional"))
    )
    (net (code "69") (name "unconnected-(U2-P1015-Pad36)") (class "Default")
      (node (ref "U2") (pin "36") (pinfunction "P1015_36") (pintype "bidirectional"))
    )
    (net (code "70") (name "unconnected-(U2-PI013{slash}~{EXTINT}-Pad43)") (class "Default")
      (node (ref "U2") (pin "43") (pinfunction "PI013/~{EXTINT}_43") (pintype "bidirectional"))
    )
    (net (code "71") (name "unconnected-(U2-RXD{slash}MOSI-Pad22)") (class "Default")
      (node (ref "U2") (pin "22") (pinfunction "RXD/MOSI_22") (pintype "bidirectional"))
    )
    (net (code "72") (name "unconnected-(U2-SQI_O-Pad30)") (class "Default")
      (node (ref "U2") (pin "30") (pinfunction "SQI_O_30") (pintype "no_connect"))
    )
    (net (code "73") (name "unconnected-(U2-SQI_O-Pad45)") (class "Default")
      (node (ref "U2") (pin "45") (pinfunction "SQI_O_45") (pintype "no_connect"))
    )
    (net (code "74") (name "unconnected-(U2-TIMEPULSE-Pad33)") (class "Default")
      (node (ref "U2") (pin "33") (pinfunction "TIMEPULSE_33") (pintype "bidirectional"))
    )
    (net (code "75") (name "unconnected-(U2-TXD{slash}MISO-Pad21)") (class "Default")
      (node (ref "U2") (pin "21") (pinfunction "TXD/MISO_21") (pintype "bidirectional"))
    )
    (net (code "76") (name "unconnected-(U2-~{RESET}-Pad20)") (class "Default")
      (node (ref "U2") (pin "20") (pinfunction "~{RESET}_20") (pintype "bidirectional"))
    )
    (net (code "77") (name "unconnected-(U2-~{SAFEBOOT}-Pad34)") (class "Default")
      (node (ref "U2") (pin "34") (pinfunction "~{SAFEBOOT}_34") (pintype "bidirectional"))
    )
    (net (code "78") (name "unconnected-(U3-1_NC-Pad3)") (class "Default")
      (node (ref "U3") (pin "3") (pinfunction "1_NC_3") (pintype "bidirectional"))
    )
    (net (code "79") (name "unconnected-(U3-2_NC-Pad4)") (class "Default")
      (node (ref "U3") (pin "4") (pinfunction "2_NC_4") (pintype "bidirectional"))
    )
    (net (code "80") (name "unconnected-(U3-3_NC-Pad5)") (class "Default")
      (node (ref "U3") (pin "5") (pinfunction "3_NC_5") (pintype "bidirectional"))
    )
    (net (code "81") (name "unconnected-(U4-BATT-PadP$14)") (class "Default")
      (node (ref "U4") (pin "P$14") (pinfunction "BATT_P$14") (pintype "bidirectional"))
    )
    (net (code "82") (name "unconnected-(U4-BATT_CHG-PadP$7)") (class "Default")
      (node (ref "U4") (pin "P$7") (pinfunction "BATT_CHG_P$7") (pintype "open_collector"))
    )
    (net (code "83") (name "unconnected-(U4-BATT_CONN-PadP$8)") (class "Default")
      (node (ref "U4") (pin "P$8") (pinfunction "BATT_CONN_P$8") (pintype "open_collector"))
    )
    (net (code "84") (name "unconnected-(U4-CONF-PadP$13)") (class "Default")
      (node (ref "U4") (pin "P$13") (pinfunction "CONF_P$13") (pintype "input"))
    )
    (net (code "85") (name "unconnected-(U4-EOC-PadP$9)") (class "Default")
      (node (ref "U4") (pin "P$9") (pinfunction "EOC_P$9") (pintype "input"))
    )
    (net (code "86") (name "unconnected-(U4-LDO1-PadP$11)") (class "Default")
      (node (ref "U4") (pin "P$11") (pinfunction "LDO1_P$11") (pintype "output"))
    )
    (net (code "87") (name "unconnected-(U4-LDO1_EN-PadP$5)") (class "Default")
      (node (ref "U4") (pin "P$5") (pinfunction "LDO1_EN_P$5") (pintype "input"))
    )
    (net (code "88") (name "unconnected-(U4-LDO2-PadP$12)") (class "Default")
      (node (ref "U4") (pin "P$12") (pinfunction "LDO2_P$12") (pintype "output"))
    )
    (net (code "89") (name "unconnected-(U4-LDO2_EN-PadP$6)") (class "Default")
      (node (ref "U4") (pin "P$6") (pinfunction "LDO2_EN_P$6") (pintype "input"))
    )
    (net (code "90") (name "unconnected-(U4-MPP-PadP$1)") (class "Default")
      (node (ref "U4") (pin "P$1") (pinfunction "MPP_P$1") (pintype "input"))
    )
    (net (code "91") (name "unconnected-(U4-MPP_REF-PadP$3)") (class "Default")
      (node (ref "U4") (pin "P$3") (pinfunction "MPP_REF_P$3") (pintype "input"))
    )
    (net (code "92") (name "unconnected-(U4-MPP_SET-PadP$2)") (class "Default")
      (node (ref "U4") (pin "P$2") (pinfunction "MPP_SET_P$2") (pintype "input"))
    )
    (net (code "93") (name "unconnected-(U4-STORE-PadP$15)") (class "Default")
      (node (ref "U4") (pin "P$15") (pinfunction "STORE_P$15") (pintype "bidirectional"))
    )
    (net (code "94") (name "unconnected-(U4-UVP-PadP$10)") (class "Default")
      (node (ref "U4") (pin "P$10") (pinfunction "UVP_P$10") (pintype "input"))
    )
    (net (code "95") (name "unconnected-(U5-~{CS}-Pad2)") (class "Default")
      (node (ref "U5") (pin "2") (pinfunction "~{CS}_2") (pintype "bidirectional"))
    )
  )
)
